# MicrocontrollerModule.net
KiCad netlist of a schematic drawn in EAGLE
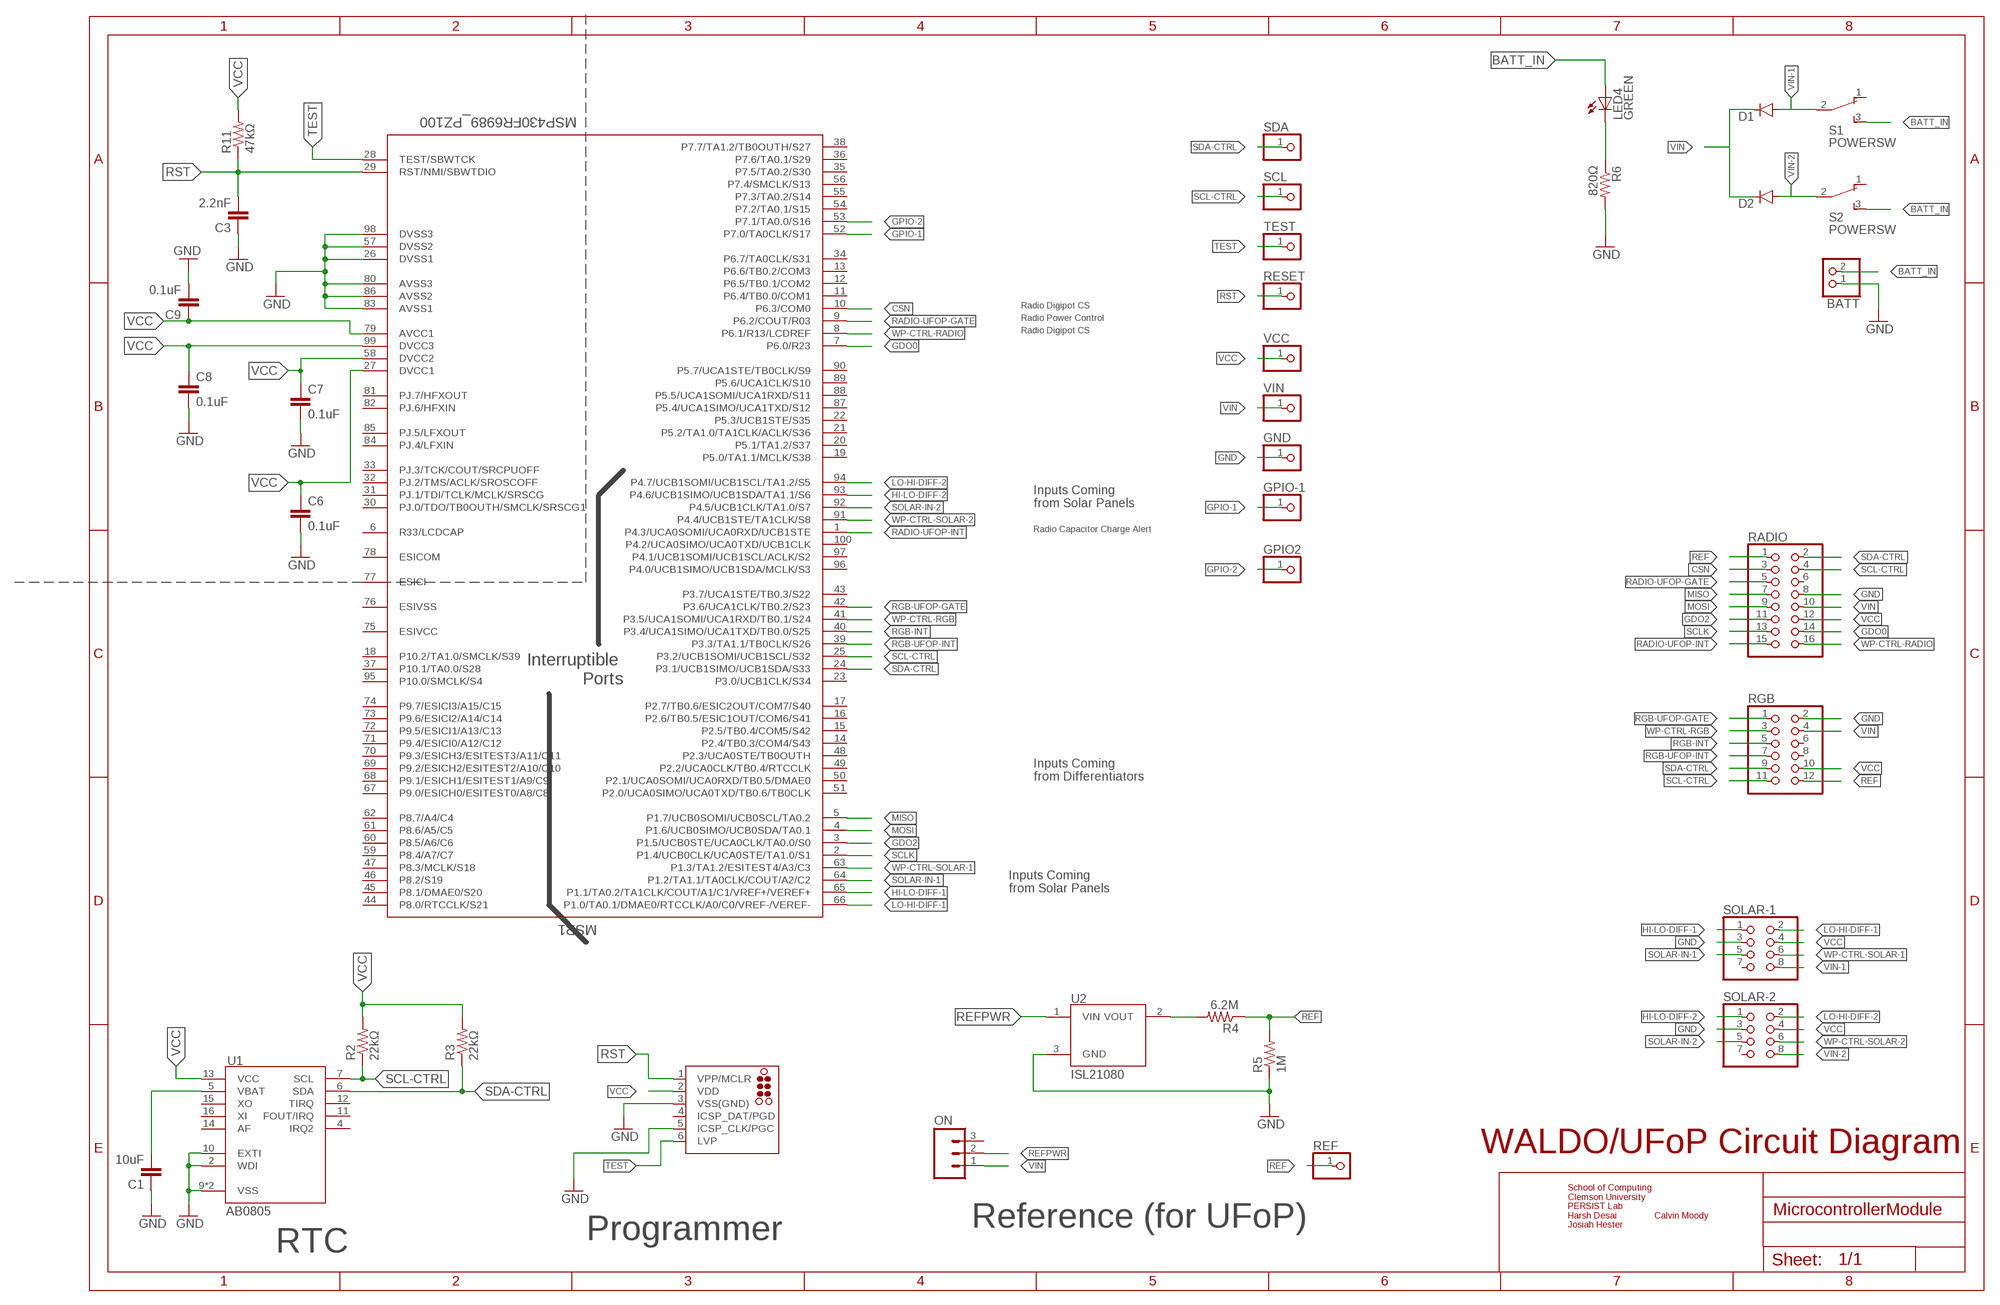
[diagram p0: schematic, sheet 1]

(export (version "E")
  (design (tool "Eeschema 10.0.6"))
  (components
    (comp (ref "BATT")
      (value "PINHD-1X2")
      (footprint "eagle-import:1X02")
      (libsource (lib "eagle-import") (part "PINHD-1X2"))
    )
    (comp (ref "C1")
      (value "10uF")
      (footprint "eagle-import:0805")
      (libsource (lib "eagle-import") (part "CAP0805"))
    )
    (comp (ref "C3")
      (value "2.2nF")
      (footprint "eagle-import:0805")
      (libsource (lib "eagle-import") (part "CAP0805"))
    )
    (comp (ref "C6")
      (value "0.1uF")
      (footprint "eagle-import:0805")
      (libsource (lib "eagle-import") (part "CAP0805"))
    )
    (comp (ref "C7")
      (value "0.1uF")
      (footprint "eagle-import:0805")
      (libsource (lib "eagle-import") (part "CAP0805"))
    )
    (comp (ref "C8")
      (value "0.1uF")
      (footprint "eagle-import:0805")
      (libsource (lib "eagle-import") (part "CAP0805"))
    )
    (comp (ref "C9")
      (value "0.1uF")
      (footprint "eagle-import:0805")
      (libsource (lib "eagle-import") (part "CAP0805"))
    )
    (comp (ref "D1")
      (value "DIODESOD523")
      (footprint "eagle-import:SOD523")
      (libsource (lib "eagle-import") (part "DIODESOD523"))
    )
    (comp (ref "D2")
      (value "DIODESOD523")
      (footprint "eagle-import:SOD523")
      (libsource (lib "eagle-import") (part "DIODESOD523"))
    )
    (comp (ref "GND")
      (value "PINHD-1X1")
      (footprint "eagle-import:1X01")
      (libsource (lib "eagle-import") (part "PINHD-1X1"))
    )
    (comp (ref "GPIO-1")
      (value "PINHD-1X1")
      (footprint "eagle-import:1X01")
      (libsource (lib "eagle-import") (part "PINHD-1X1"))
    )
    (comp (ref "GPIO2")
      (value "PINHD-1X1")
      (footprint "eagle-import:1X01")
      (libsource (lib "eagle-import") (part "PINHD-1X1"))
    )
    (comp (ref "J1")
      (value "TC2030-MCP-NL")
      (footprint "eagle-import:TC2030-MCP-NL")
      (libsource (lib "eagle-import") (part "TC2030-MCP-NL"))
    )
    (comp (ref "LED4")
      (value "GREEN")
      (footprint "eagle-import:CHIP-LED0805")
      (libsource (lib "eagle-import") (part "LEDCHIP-LED0805"))
    )
    (comp (ref "MSP1")
      (value "MSP430FR6989_PZ100")
      (footprint "eagle-import:PZ100")
      (libsource (lib "eagle-import") (part "MSP430FR6989_PZ100"))
    )
    (comp (ref "ON")
      (value "M03")
      (footprint "eagle-import:1X03-1.27MM")
      (libsource (lib "eagle-import") (part "M03"))
    )
    (comp (ref "R2")
      (value "22kΩ")
      (footprint "eagle-import:0805")
      (libsource (lib "eagle-import") (part "RESISTOR0805-RES"))
    )
    (comp (ref "R3")
      (value "22kΩ")
      (footprint "eagle-import:0805")
      (libsource (lib "eagle-import") (part "RESISTOR0805-RES"))
    )
    (comp (ref "R4")
      (value "6.2M")
      (footprint "eagle-import:0805")
      (libsource (lib "eagle-import") (part "RESISTOR0805-RES"))
    )
    (comp (ref "R5")
      (value "1M")
      (footprint "eagle-import:0805")
      (libsource (lib "eagle-import") (part "RESISTOR0805-RES"))
    )
    (comp (ref "R6")
      (value "820Ω")
      (footprint "eagle-import:0805")
      (libsource (lib "eagle-import") (part "RESISTOR0805-RES"))
    )
    (comp (ref "R11")
      (value "47kΩ")
      (footprint "eagle-import:0805")
      (libsource (lib "eagle-import") (part "RESISTOR0805-RES"))
    )
    (comp (ref "RADIO")
      (value "PINHD-2X8/90")
      (footprint "eagle-import:2X08_90")
      (libsource (lib "eagle-import") (part "PINHD-2X8/90"))
    )
    (comp (ref "REF")
      (value "PINHD-1X1")
      (footprint "eagle-import:1X01")
      (libsource (lib "eagle-import") (part "PINHD-1X1"))
    )
    (comp (ref "RESET")
      (value "PINHD-1X1")
      (footprint "eagle-import:1X01")
      (libsource (lib "eagle-import") (part "PINHD-1X1"))
    )
    (comp (ref "RGB")
      (value "PINHD-2X6/90")
      (footprint "eagle-import:2X06_90")
      (libsource (lib "eagle-import") (part "PINHD-2X6/90"))
    )
    (comp (ref "S1")
      (value "POWERSW")
      (footprint "eagle-import:TL3XYO")
      (libsource (lib "eagle-import") (part "POWERSW"))
    )
    (comp (ref "S2")
      (value "POWERSW")
      (footprint "eagle-import:TL3XYO")
      (libsource (lib "eagle-import") (part "POWERSW"))
    )
    (comp (ref "SCL")
      (value "PINHD-1X1")
      (footprint "eagle-import:1X01")
      (libsource (lib "eagle-import") (part "PINHD-1X1"))
    )
    (comp (ref "SDA")
      (value "PINHD-1X1")
      (footprint "eagle-import:1X01")
      (libsource (lib "eagle-import") (part "PINHD-1X1"))
    )
    (comp (ref "SOLAR-1")
      (value "PINHD-2X4/90")
      (footprint "eagle-import:2X04_90")
      (libsource (lib "eagle-import") (part "PINHD-2X4/90"))
    )
    (comp (ref "SOLAR-2")
      (value "PINHD-2X4/90")
      (footprint "eagle-import:2X04_90")
      (libsource (lib "eagle-import") (part "PINHD-2X4/90"))
    )
    (comp (ref "TEST")
      (value "PINHD-1X1")
      (footprint "eagle-import:1X01")
      (libsource (lib "eagle-import") (part "PINHD-1X1"))
    )
    (comp (ref "U1")
      (value "AB0805")
      (footprint "eagle-import:QFN16")
      (libsource (lib "eagle-import") (part "AB0805"))
    )
    (comp (ref "U2")
      (value "ISL21080")
      (footprint "eagle-import:SOT-23")
      (libsource (lib "eagle-import") (part "ISL21080"))
    )
    (comp (ref "VCC")
      (value "PINHD-1X1")
      (footprint "eagle-import:1X01")
      (libsource (lib "eagle-import") (part "PINHD-1X1"))
    )
    (comp (ref "VIN")
      (value "PINHD-1X1")
      (footprint "eagle-import:1X01")
      (libsource (lib "eagle-import") (part "PINHD-1X1"))
    )
  )
  (nets
    (net (code "1") (name "BATT_IN") (class "Default")
      (node (ref "BATT") (pin "2") (pinfunction "2_2") (pintype "passive"))
      (node (ref "LED4") (pin "A") (pinfunction "A_A") (pintype "passive"))
      (node (ref "S1") (pin "3") (pinfunction "S_3") (pintype "passive"))
      (node (ref "S2") (pin "3") (pinfunction "S_3") (pintype "passive"))
    )
    (net (code "2") (name "CSN") (class "Default")
      (node (ref "MSP1") (pin "10") (pinfunction "P6.3/COM0_10") (pintype "bidirectional"))
      (node (ref "RADIO") (pin "3") (pinfunction "3_3") (pintype "passive"))
    )
    (net (code "3") (name "GDO0") (class "Default")
      (node (ref "MSP1") (pin "7") (pinfunction "P6.0/R23_7") (pintype "bidirectional"))
      (node (ref "RADIO") (pin "14") (pinfunction "14_14") (pintype "passive"))
    )
    (net (code "4") (name "GDO2") (class "Default")
      (node (ref "MSP1") (pin "3") (pinfunction "P1.5/UCB0STE/UCA0CLK/TA0.0/S0_3") (pintype "bidirectional"))
      (node (ref "RADIO") (pin "11") (pinfunction "11_11") (pintype "passive"))
    )
    (net (code "5") (name "GND") (class "Default")
      (node (ref "BATT") (pin "1") (pinfunction "1_1") (pintype "passive"))
      (node (ref "C1") (pin "1") (pinfunction "1_1") (pintype "passive"))
      (node (ref "C3") (pin "1") (pinfunction "1_1") (pintype "passive"))
      (node (ref "C6") (pin "2") (pinfunction "2_2") (pintype "passive"))
      (node (ref "C7") (pin "2") (pinfunction "2_2") (pintype "passive"))
      (node (ref "C8") (pin "2") (pinfunction "2_2") (pintype "passive"))
      (node (ref "C9") (pin "2") (pinfunction "2_2") (pintype "passive"))
      (node (ref "GND") (pin "1") (pinfunction "1_1") (pintype "passive"))
      (node (ref "J1") (pin "3") (pinfunction "VSS(GND)_3") (pintype "power_in"))
      (node (ref "J1") (pin "5") (pinfunction "ICSP_CLK/PGC_5") (pintype "output"))
      (node (ref "MSP1") (pin "26") (pinfunction "DVSS1_26") (pintype "bidirectional"))
      (node (ref "MSP1") (pin "57") (pinfunction "DVSS2_57") (pintype "bidirectional"))
      (node (ref "MSP1") (pin "80") (pinfunction "AVSS3_80") (pintype "bidirectional"))
      (node (ref "MSP1") (pin "83") (pinfunction "AVSS1_83") (pintype "bidirectional"))
      (node (ref "MSP1") (pin "86") (pinfunction "AVSS2_86") (pintype "bidirectional"))
      (node (ref "MSP1") (pin "98") (pinfunction "DVSS3_98") (pintype "bidirectional"))
      (node (ref "R5") (pin "1") (pinfunction "1_1") (pintype "passive"))
      (node (ref "R6") (pin "2") (pinfunction "2_2") (pintype "passive"))
      (node (ref "RADIO") (pin "8") (pinfunction "8_8") (pintype "passive"))
      (node (ref "RGB") (pin "2") (pinfunction "2_2") (pintype "passive"))
      (node (ref "SOLAR-1") (pin "3") (pinfunction "3_3") (pintype "passive"))
      (node (ref "SOLAR-2") (pin "3") (pinfunction "3_3") (pintype "passive"))
      (node (ref "U1") (pin "10") (pinfunction "EXTI_10") (pintype "bidirectional"))
      (node (ref "U1") (pin "2") (pinfunction "WDI_2") (pintype "bidirectional"))
      (node (ref "U1") (pin "9") (pinfunction "VSS_9") (pintype "bidirectional"))
      (node (ref "U1") (pin "TH") (pinfunction "VSS_TH") (pintype "bidirectional"))
      (node (ref "U2") (pin "3") (pinfunction "GND_3") (pintype "bidirectional"))
    )
    (net (code "6") (name "GPIO-1") (class "Default")
      (node (ref "GPIO-1") (pin "1") (pinfunction "1_1") (pintype "passive"))
      (node (ref "MSP1") (pin "52") (pinfunction "P7.0/TA0CLK/S17_52") (pintype "bidirectional"))
    )
    (net (code "7") (name "GPIO-2") (class "Default")
      (node (ref "GPIO2") (pin "1") (pinfunction "1_1") (pintype "passive"))
      (node (ref "MSP1") (pin "53") (pinfunction "P7.1/TA0.0/S16_53") (pintype "bidirectional"))
    )
    (net (code "8") (name "HI-LO-DIFF-1") (class "Default")
      (node (ref "MSP1") (pin "65") (pinfunction "P1.1/TA0.2/TA1CLK/COUT/A1/C1/VREF+/VEREF+_65") (pintype "bidirectional"))
      (node (ref "SOLAR-1") (pin "1") (pinfunction "1_1") (pintype "passive"))
    )
    (net (code "9") (name "HI-LO-DIFF-2") (class "Default")
      (node (ref "MSP1") (pin "93") (pinfunction "P4.6/UCB1SIMO/UCB1SDA/TA1.1/S6_93") (pintype "bidirectional"))
      (node (ref "SOLAR-2") (pin "1") (pinfunction "1_1") (pintype "passive"))
    )
    (net (code "10") (name "LO-HI-DIFF-1") (class "Default")
      (node (ref "MSP1") (pin "66") (pinfunction "P1.0/TA0.1/DMAE0/RTCCLK/A0/C0/VREF-/VEREF-_66") (pintype "bidirectional"))
      (node (ref "SOLAR-1") (pin "2") (pinfunction "2_2") (pintype "passive"))
    )
    (net (code "11") (name "LO-HI-DIFF-2") (class "Default")
      (node (ref "MSP1") (pin "94") (pinfunction "P4.7/UCB1SOMI/UCB1SCL/TA1.2/S5_94") (pintype "bidirectional"))
      (node (ref "SOLAR-2") (pin "2") (pinfunction "2_2") (pintype "passive"))
    )
    (net (code "12") (name "MISO") (class "Default")
      (node (ref "MSP1") (pin "5") (pinfunction "P1.7/UCB0SOMI/UCB0SCL/TA0.2_5") (pintype "bidirectional"))
      (node (ref "RADIO") (pin "7") (pinfunction "7_7") (pintype "passive"))
    )
    (net (code "13") (name "MOSI") (class "Default")
      (node (ref "MSP1") (pin "4") (pinfunction "P1.6/UCB0SIMO/UCB0SDA/TA0.1_4") (pintype "bidirectional"))
      (node (ref "RADIO") (pin "9") (pinfunction "9_9") (pintype "passive"))
    )
    (net (code "14") (name "Net-(LED4-PadC)") (class "Default")
      (node (ref "LED4") (pin "C") (pinfunction "C_C") (pintype "passive"))
      (node (ref "R6") (pin "1") (pinfunction "1_1") (pintype "passive"))
    )
    (net (code "15") (name "Net-(U1-VBAT)") (class "Default")
      (node (ref "C1") (pin "2") (pinfunction "2_2") (pintype "passive"))
      (node (ref "U1") (pin "5") (pinfunction "VBAT_5") (pintype "bidirectional"))
    )
    (net (code "16") (name "Net-(U2-VOUT)") (class "Default")
      (node (ref "R4") (pin "2") (pinfunction "2_2") (pintype "passive"))
      (node (ref "U2") (pin "2") (pinfunction "VOUT_2") (pintype "bidirectional"))
    )
    (net (code "17") (name "RADIO-UFOP-GATE") (class "Default")
      (node (ref "MSP1") (pin "9") (pinfunction "P6.2/COUT/R03_9") (pintype "bidirectional"))
      (node (ref "RADIO") (pin "5") (pinfunction "5_5") (pintype "passive"))
    )
    (net (code "18") (name "RADIO-UFOP-INT") (class "Default")
      (node (ref "MSP1") (pin "1") (pinfunction "P4.3/UCA0SOMI/UCA0RXD/UCB1STE_1") (pintype "bidirectional"))
      (node (ref "RADIO") (pin "15") (pinfunction "15_15") (pintype "passive"))
    )
    (net (code "19") (name "REF") (class "Default")
      (node (ref "R4") (pin "1") (pinfunction "1_1") (pintype "passive"))
      (node (ref "R5") (pin "2") (pinfunction "2_2") (pintype "passive"))
      (node (ref "RADIO") (pin "1") (pinfunction "1_1") (pintype "passive"))
      (node (ref "REF") (pin "1") (pinfunction "1_1") (pintype "passive"))
      (node (ref "RGB") (pin "12") (pinfunction "12_12") (pintype "passive"))
    )
    (net (code "20") (name "REFPWR") (class "Default")
      (node (ref "ON") (pin "2") (pinfunction "2_2") (pintype "passive"))
      (node (ref "U2") (pin "1") (pinfunction "VIN_1") (pintype "bidirectional"))
    )
    (net (code "21") (name "RGB-INT") (class "Default")
      (node (ref "MSP1") (pin "40") (pinfunction "P3.4/UCA1SIMO/UCA1TXD/TB0.0/S25_40") (pintype "bidirectional"))
      (node (ref "RGB") (pin "5") (pinfunction "5_5") (pintype "passive"))
    )
    (net (code "22") (name "RGB-UFOP-GATE") (class "Default")
      (node (ref "MSP1") (pin "42") (pinfunction "P3.6/UCA1CLK/TB0.2/S23_42") (pintype "bidirectional"))
      (node (ref "RGB") (pin "1") (pinfunction "1_1") (pintype "passive"))
    )
    (net (code "23") (name "RGB-UFOP-INT") (class "Default")
      (node (ref "MSP1") (pin "39") (pinfunction "P3.3/TA1.1/TB0CLK/S26_39") (pintype "bidirectional"))
      (node (ref "RGB") (pin "7") (pinfunction "7_7") (pintype "passive"))
    )
    (net (code "24") (name "RST") (class "Default")
      (node (ref "C3") (pin "2") (pinfunction "2_2") (pintype "passive"))
      (node (ref "J1") (pin "1") (pinfunction "VPP/MCLR_1") (pintype "passive"))
      (node (ref "MSP1") (pin "29") (pinfunction "RST/NMI/SBWTDIO_29") (pintype "bidirectional"))
      (node (ref "R11") (pin "1") (pinfunction "1_1") (pintype "passive"))
      (node (ref "RESET") (pin "1") (pinfunction "1_1") (pintype "passive"))
    )
    (net (code "25") (name "SCL-CTRL") (class "Default")
      (node (ref "MSP1") (pin "25") (pinfunction "P3.2/UCB1SOMI/UCB1SCL/S32_25") (pintype "bidirectional"))
      (node (ref "R2") (pin "1") (pinfunction "1_1") (pintype "passive"))
      (node (ref "RADIO") (pin "4") (pinfunction "4_4") (pintype "passive"))
      (node (ref "RGB") (pin "11") (pinfunction "11_11") (pintype "passive"))
      (node (ref "SCL") (pin "1") (pinfunction "1_1") (pintype "passive"))
      (node (ref "U1") (pin "7") (pinfunction "SCL_7") (pintype "bidirectional"))
    )
    (net (code "26") (name "SCLK") (class "Default")
      (node (ref "MSP1") (pin "2") (pinfunction "P1.4/UCB0CLK/UCA0STE/TA1.0/S1_2") (pintype "bidirectional"))
      (node (ref "RADIO") (pin "13") (pinfunction "13_13") (pintype "passive"))
    )
    (net (code "27") (name "SDA-CTRL") (class "Default")
      (node (ref "MSP1") (pin "24") (pinfunction "P3.1/UCB1SIMO/UCB1SDA/S33_24") (pintype "bidirectional"))
      (node (ref "R3") (pin "1") (pinfunction "1_1") (pintype "passive"))
      (node (ref "RADIO") (pin "2") (pinfunction "2_2") (pintype "passive"))
      (node (ref "RGB") (pin "9") (pinfunction "9_9") (pintype "passive"))
      (node (ref "SDA") (pin "1") (pinfunction "1_1") (pintype "passive"))
      (node (ref "U1") (pin "6") (pinfunction "SDA_6") (pintype "bidirectional"))
    )
    (net (code "28") (name "SOLAR-IN-1") (class "Default")
      (node (ref "MSP1") (pin "64") (pinfunction "P1.2/TA1.1/TA0CLK/COUT/A2/C2_64") (pintype "bidirectional"))
      (node (ref "SOLAR-1") (pin "5") (pinfunction "5_5") (pintype "passive"))
    )
    (net (code "29") (name "SOLAR-IN-2") (class "Default")
      (node (ref "MSP1") (pin "92") (pinfunction "P4.5/UCB1CLK/TA1.0/S7_92") (pintype "bidirectional"))
      (node (ref "SOLAR-2") (pin "5") (pinfunction "5_5") (pintype "passive"))
    )
    (net (code "30") (name "TEST") (class "Default")
      (node (ref "J1") (pin "6") (pinfunction "LVP_6") (pintype "bidirectional"))
      (node (ref "MSP1") (pin "28") (pinfunction "TEST/SBWTCK_28") (pintype "bidirectional"))
      (node (ref "TEST") (pin "1") (pinfunction "1_1") (pintype "passive"))
    )
    (net (code "31") (name "VCC") (class "Default")
      (node (ref "C6") (pin "1") (pinfunction "1_1") (pintype "passive"))
      (node (ref "C7") (pin "1") (pinfunction "1_1") (pintype "passive"))
      (node (ref "C8") (pin "1") (pinfunction "1_1") (pintype "passive"))
      (node (ref "C9") (pin "1") (pinfunction "1_1") (pintype "passive"))
      (node (ref "J1") (pin "2") (pinfunction "VDD_2") (pintype "power_in"))
      (node (ref "MSP1") (pin "27") (pinfunction "DVCC1_27") (pintype "bidirectional"))
      (node (ref "MSP1") (pin "58") (pinfunction "DVCC2_58") (pintype "bidirectional"))
      (node (ref "MSP1") (pin "79") (pinfunction "AVCC1_79") (pintype "bidirectional"))
      (node (ref "MSP1") (pin "99") (pinfunction "DVCC3_99") (pintype "bidirectional"))
      (node (ref "R11") (pin "2") (pinfunction "2_2") (pintype "passive"))
      (node (ref "R2") (pin "2") (pinfunction "2_2") (pintype "passive"))
      (node (ref "R3") (pin "2") (pinfunction "2_2") (pintype "passive"))
      (node (ref "RADIO") (pin "12") (pinfunction "12_12") (pintype "passive"))
      (node (ref "RGB") (pin "10") (pinfunction "10_10") (pintype "passive"))
      (node (ref "SOLAR-1") (pin "4") (pinfunction "4_4") (pintype "passive"))
      (node (ref "SOLAR-2") (pin "4") (pinfunction "4_4") (pintype "passive"))
      (node (ref "U1") (pin "13") (pinfunction "VCC_13") (pintype "bidirectional"))
      (node (ref "VCC") (pin "1") (pinfunction "1_1") (pintype "passive"))
    )
    (net (code "32") (name "VIN") (class "Default")
      (node (ref "D1") (pin "C") (pinfunction "C_C") (pintype "passive"))
      (node (ref "D2") (pin "C") (pinfunction "C_C") (pintype "passive"))
      (node (ref "ON") (pin "1") (pinfunction "1_1") (pintype "passive"))
      (node (ref "RADIO") (pin "10") (pinfunction "10_10") (pintype "passive"))
      (node (ref "RGB") (pin "4") (pinfunction "4_4") (pintype "passive"))
      (node (ref "VIN") (pin "1") (pinfunction "1_1") (pintype "passive"))
    )
    (net (code "33") (name "VIN-1") (class "Default")
      (node (ref "D1") (pin "A") (pinfunction "A_A") (pintype "passive"))
      (node (ref "S1") (pin "2") (pinfunction "P_2") (pintype "passive"))
      (node (ref "SOLAR-1") (pin "8") (pinfunction "8_8") (pintype "passive"))
    )
    (net (code "34") (name "VIN-2") (class "Default")
      (node (ref "D2") (pin "A") (pinfunction "A_A") (pintype "passive"))
      (node (ref "S2") (pin "2") (pinfunction "P_2") (pintype "passive"))
      (node (ref "SOLAR-2") (pin "8") (pinfunction "8_8") (pintype "passive"))
    )
    (net (code "35") (name "WP-CTRL-RADIO") (class "Default")
      (node (ref "MSP1") (pin "8") (pinfunction "P6.1/R13/LCDREF_8") (pintype "bidirectional"))
      (node (ref "RADIO") (pin "16") (pinfunction "16_16") (pintype "passive"))
    )
    (net (code "36") (name "WP-CTRL-RGB") (class "Default")
      (node (ref "MSP1") (pin "41") (pinfunction "P3.5/UCA1SOMI/UCA1RXD/TB0.1/S24_41") (pintype "bidirectional"))
      (node (ref "RGB") (pin "3") (pinfunction "3_3") (pintype "passive"))
    )
    (net (code "37") (name "WP-CTRL-SOLAR-1") (class "Default")
      (node (ref "MSP1") (pin "63") (pinfunction "P1.3/TA1.2/ESITEST4/A3/C3_63") (pintype "bidirectional"))
      (node (ref "SOLAR-1") (pin "6") (pinfunction "6_6") (pintype "passive"))
    )
    (net (code "38") (name "WP-CTRL-SOLAR-2") (class "Default")
      (node (ref "MSP1") (pin "91") (pinfunction "P4.4/UCB1STE/TA1CLK/S8_91") (pintype "bidirectional"))
      (node (ref "SOLAR-2") (pin "6") (pinfunction "6_6") (pintype "passive"))
    )
    (net (code "39") (name "unconnected-(J1-ICSP_DAT{slash}PGD-Pad4)") (class "Default")
      (node (ref "J1") (pin "4") (pinfunction "ICSP_DAT/PGD_4") (pintype "bidirectional"))
    )
    (net (code "40") (name "unconnected-(MSP1-ESICI-Pad77)") (class "Default")
      (node (ref "MSP1") (pin "77") (pinfunction "ESICI_77") (pintype "bidirectional"))
    )
    (net (code "41") (name "unconnected-(MSP1-ESICOM-Pad78)") (class "Default")
      (node (ref "MSP1") (pin "78") (pinfunction "ESICOM_78") (pintype "bidirectional"))
    )
    (net (code "42") (name "unconnected-(MSP1-ESIVCC-Pad75)") (class "Default")
      (node (ref "MSP1") (pin "75") (pinfunction "ESIVCC_75") (pintype "bidirectional"))
    )
    (net (code "43") (name "unconnected-(MSP1-ESIVSS-Pad76)") (class "Default")
      (node (ref "MSP1") (pin "76") (pinfunction "ESIVSS_76") (pintype "bidirectional"))
    )
    (net (code "44") (name "unconnected-(MSP1-P2.0{slash}UCA0SIMO{slash}UCA0TXD{slash}TB0.6{slash}TB0CLK-Pad51)") (class "Default")
      (node (ref "MSP1") (pin "51") (pinfunction "P2.0/UCA0SIMO/UCA0TXD/TB0.6/TB0CLK_51") (pintype "bidirectional"))
    )
    (net (code "45") (name "unconnected-(MSP1-P2.1{slash}UCA0SOMI{slash}UCA0RXD{slash}TB0.5{slash}DMAE0-Pad50)") (class "Default")
      (node (ref "MSP1") (pin "50") (pinfunction "P2.1/UCA0SOMI/UCA0RXD/TB0.5/DMAE0_50") (pintype "bidirectional"))
    )
    (net (code "46") (name "unconnected-(MSP1-P2.2{slash}UCA0CLK{slash}TB0.4{slash}RTCCLK-Pad49)") (class "Default")
      (node (ref "MSP1") (pin "49") (pinfunction "P2.2/UCA0CLK/TB0.4/RTCCLK_49") (pintype "bidirectional"))
    )
    (net (code "47") (name "unconnected-(MSP1-P2.3{slash}UCA0STE{slash}TB0OUTH-Pad48)") (class "Default")
      (node (ref "MSP1") (pin "48") (pinfunction "P2.3/UCA0STE/TB0OUTH_48") (pintype "bidirectional"))
    )
    (net (code "48") (name "unconnected-(MSP1-P2.4{slash}TB0.3{slash}COM4{slash}S43-Pad14)") (class "Default")
      (node (ref "MSP1") (pin "14") (pinfunction "P2.4/TB0.3/COM4/S43_14") (pintype "bidirectional"))
    )
    (net (code "49") (name "unconnected-(MSP1-P2.5{slash}TB0.4{slash}COM5{slash}S42-Pad15)") (class "Default")
      (node (ref "MSP1") (pin "15") (pinfunction "P2.5/TB0.4/COM5/S42_15") (pintype "bidirectional"))
    )
    (net (code "50") (name "unconnected-(MSP1-P2.6{slash}TB0.5{slash}ESIC1OUT{slash}COM6{slash}S41-Pad16)") (class "Default")
      (node (ref "MSP1") (pin "16") (pinfunction "P2.6/TB0.5/ESIC1OUT/COM6/S41_16") (pintype "bidirectional"))
    )
    (net (code "51") (name "unconnected-(MSP1-P2.7{slash}TB0.6{slash}ESIC2OUT{slash}COM7{slash}S40-Pad17)") (class "Default")
      (node (ref "MSP1") (pin "17") (pinfunction "P2.7/TB0.6/ESIC2OUT/COM7/S40_17") (pintype "bidirectional"))
    )
    (net (code "52") (name "unconnected-(MSP1-P3.0{slash}UCB1CLK{slash}S34-Pad23)") (class "Default")
      (node (ref "MSP1") (pin "23") (pinfunction "P3.0/UCB1CLK/S34_23") (pintype "bidirectional"))
    )
    (net (code "53") (name "unconnected-(MSP1-P3.7{slash}UCA1STE{slash}TB0.3{slash}S22-Pad43)") (class "Default")
      (node (ref "MSP1") (pin "43") (pinfunction "P3.7/UCA1STE/TB0.3/S22_43") (pintype "bidirectional"))
    )
    (net (code "54") (name "unconnected-(MSP1-P4.0{slash}UCB1SIMO{slash}UCB1SDA{slash}MCLK{slash}S3-Pad96)") (class "Default")
      (node (ref "MSP1") (pin "96") (pinfunction "P4.0/UCB1SIMO/UCB1SDA/MCLK/S3_96") (pintype "bidirectional"))
    )
    (net (code "55") (name "unconnected-(MSP1-P4.1{slash}UCB1SOMI{slash}UCB1SCL{slash}ACLK{slash}S2-Pad97)") (class "Default")
      (node (ref "MSP1") (pin "97") (pinfunction "P4.1/UCB1SOMI/UCB1SCL/ACLK/S2_97") (pintype "bidirectional"))
    )
    (net (code "56") (name "unconnected-(MSP1-P4.2{slash}UCA0SIMO{slash}UCA0TXD{slash}UCB1CLK-Pad100)") (class "Default")
      (node (ref "MSP1") (pin "100") (pinfunction "P4.2/UCA0SIMO/UCA0TXD/UCB1CLK_100") (pintype "bidirectional"))
    )
    (net (code "57") (name "unconnected-(MSP1-P5.0{slash}TA1.1{slash}MCLK{slash}S38-Pad19)") (class "Default")
      (node (ref "MSP1") (pin "19") (pinfunction "P5.0/TA1.1/MCLK/S38_19") (pintype "bidirectional"))
    )
    (net (code "58") (name "unconnected-(MSP1-P5.1{slash}TA1.2{slash}S37-Pad20)") (class "Default")
      (node (ref "MSP1") (pin "20") (pinfunction "P5.1/TA1.2/S37_20") (pintype "bidirectional"))
    )
    (net (code "59") (name "unconnected-(MSP1-P5.2{slash}TA1.0{slash}TA1CLK{slash}ACLK{slash}S36-Pad21)") (class "Default")
      (node (ref "MSP1") (pin "21") (pinfunction "P5.2/TA1.0/TA1CLK/ACLK/S36_21") (pintype "bidirectional"))
    )
    (net (code "60") (name "unconnected-(MSP1-P5.3{slash}UCB1STE{slash}S35-Pad22)") (class "Default")
      (node (ref "MSP1") (pin "22") (pinfunction "P5.3/UCB1STE/S35_22") (pintype "bidirectional"))
    )
    (net (code "61") (name "unconnected-(MSP1-P5.4{slash}UCA1SIMO{slash}UCA1TXD{slash}S12-Pad87)") (class "Default")
      (node (ref "MSP1") (pin "87") (pinfunction "P5.4/UCA1SIMO/UCA1TXD/S12_87") (pintype "bidirectional"))
    )
    (net (code "62") (name "unconnected-(MSP1-P5.5{slash}UCA1SOMI{slash}UCA1RXD{slash}S11-Pad88)") (class "Default")
      (node (ref "MSP1") (pin "88") (pinfunction "P5.5/UCA1SOMI/UCA1RXD/S11_88") (pintype "bidirectional"))
    )
    (net (code "63") (name "unconnected-(MSP1-P5.6{slash}UCA1CLK{slash}S10-Pad89)") (class "Default")
      (node (ref "MSP1") (pin "89") (pinfunction "P5.6/UCA1CLK/S10_89") (pintype "bidirectional"))
    )
    (net (code "64") (name "unconnected-(MSP1-P5.7{slash}UCA1STE{slash}TB0CLK{slash}S9-Pad90)") (class "Default")
      (node (ref "MSP1") (pin "90") (pinfunction "P5.7/UCA1STE/TB0CLK/S9_90") (pintype "bidirectional"))
    )
    (net (code "65") (name "unconnected-(MSP1-P6.4{slash}TB0.0{slash}COM1-Pad11)") (class "Default")
      (node (ref "MSP1") (pin "11") (pinfunction "P6.4/TB0.0/COM1_11") (pintype "bidirectional"))
    )
    (net (code "66") (name "unconnected-(MSP1-P6.5{slash}TB0.1{slash}COM2-Pad12)") (class "Default")
      (node (ref "MSP1") (pin "12") (pinfunction "P6.5/TB0.1/COM2_12") (pintype "bidirectional"))
    )
    (net (code "67") (name "unconnected-(MSP1-P6.6{slash}TB0.2{slash}COM3-Pad13)") (class "Default")
      (node (ref "MSP1") (pin "13") (pinfunction "P6.6/TB0.2/COM3_13") (pintype "bidirectional"))
    )
    (net (code "68") (name "unconnected-(MSP1-P6.7{slash}TA0CLK{slash}S31-Pad34)") (class "Default")
      (node (ref "MSP1") (pin "34") (pinfunction "P6.7/TA0CLK/S31_34") (pintype "bidirectional"))
    )
    (net (code "69") (name "unconnected-(MSP1-P7.2{slash}TA0.1{slash}S15-Pad54)") (class "Default")
      (node (ref "MSP1") (pin "54") (pinfunction "P7.2/TA0.1/S15_54") (pintype "bidirectional"))
    )
    (net (code "70") (name "unconnected-(MSP1-P7.3{slash}TA0.2{slash}S14-Pad55)") (class "Default")
      (node (ref "MSP1") (pin "55") (pinfunction "P7.3/TA0.2/S14_55") (pintype "bidirectional"))
    )
    (net (code "71") (name "unconnected-(MSP1-P7.4{slash}SMCLK{slash}S13-Pad56)") (class "Default")
      (node (ref "MSP1") (pin "56") (pinfunction "P7.4/SMCLK/S13_56") (pintype "bidirectional"))
    )
    (net (code "72") (name "unconnected-(MSP1-P7.5{slash}TA0.2{slash}S30-Pad35)") (class "Default")
      (node (ref "MSP1") (pin "35") (pinfunction "P7.5/TA0.2/S30_35") (pintype "bidirectional"))
    )
    (net (code "73") (name "unconnected-(MSP1-P7.6{slash}TA0.1{slash}S29-Pad36)") (class "Default")
      (node (ref "MSP1") (pin "36") (pinfunction "P7.6/TA0.1/S29_36") (pintype "bidirectional"))
    )
    (net (code "74") (name "unconnected-(MSP1-P7.7{slash}TA1.2{slash}TB0OUTH{slash}S27-Pad38)") (class "Default")
      (node (ref "MSP1") (pin "38") (pinfunction "P7.7/TA1.2/TB0OUTH/S27_38") (pintype "bidirectional"))
    )
    (net (code "75") (name "unconnected-(MSP1-P8.0{slash}RTCCLK{slash}S21-Pad44)") (class "Default")
      (node (ref "MSP1") (pin "44") (pinfunction "P8.0/RTCCLK/S21_44") (pintype "bidirectional"))
    )
    (net (code "76") (name "unconnected-(MSP1-P8.1{slash}DMAE0{slash}S20-Pad45)") (class "Default")
      (node (ref "MSP1") (pin "45") (pinfunction "P8.1/DMAE0/S20_45") (pintype "bidirectional"))
    )
    (net (code "77") (name "unconnected-(MSP1-P8.2{slash}S19-Pad46)") (class "Default")
      (node (ref "MSP1") (pin "46") (pinfunction "P8.2/S19_46") (pintype "bidirectional"))
    )
    (net (code "78") (name "unconnected-(MSP1-P8.3{slash}MCLK{slash}S18-Pad47)") (class "Default")
      (node (ref "MSP1") (pin "47") (pinfunction "P8.3/MCLK/S18_47") (pintype "bidirectional"))
    )
    (net (code "79") (name "unconnected-(MSP1-P8.4{slash}A7{slash}C7-Pad59)") (class "Default")
      (node (ref "MSP1") (pin "59") (pinfunction "P8.4/A7/C7_59") (pintype "bidirectional"))
    )
    (net (code "80") (name "unconnected-(MSP1-P8.5{slash}A6{slash}C6-Pad60)") (class "Default")
      (node (ref "MSP1") (pin "60") (pinfunction "P8.5/A6/C6_60") (pintype "bidirectional"))
    )
    (net (code "81") (name "unconnected-(MSP1-P8.6{slash}A5{slash}C5-Pad61)") (class "Default")
      (node (ref "MSP1") (pin "61") (pinfunction "P8.6/A5/C5_61") (pintype "bidirectional"))
    )
    (net (code "82") (name "unconnected-(MSP1-P8.7{slash}A4{slash}C4-Pad62)") (class "Default")
      (node (ref "MSP1") (pin "62") (pinfunction "P8.7/A4/C4_62") (pintype "bidirectional"))
    )
    (net (code "83") (name "unconnected-(MSP1-P9.0{slash}ESICH0{slash}ESITEST0{slash}A8{slash}C8-Pad67)") (class "Default")
      (node (ref "MSP1") (pin "67") (pinfunction "P9.0/ESICH0/ESITEST0/A8/C8_67") (pintype "bidirectional"))
    )
    (net (code "84") (name "unconnected-(MSP1-P9.1{slash}ESICH1{slash}ESITEST1{slash}A9{slash}C9-Pad68)") (class "Default")
      (node (ref "MSP1") (pin "68") (pinfunction "P9.1/ESICH1/ESITEST1/A9/C9_68") (pintype "bidirectional"))
    )
    (net (code "85") (name "unconnected-(MSP1-P9.2{slash}ESICH2{slash}ESITEST2{slash}A10{slash}C10-Pad69)") (class "Default")
      (node (ref "MSP1") (pin "69") (pinfunction "P9.2/ESICH2/ESITEST2/A10/C10_69") (pintype "bidirectional"))
    )
    (net (code "86") (name "unconnected-(MSP1-P9.3{slash}ESICH3{slash}ESITEST3{slash}A11{slash}C11-Pad70)") (class "Default")
      (node (ref "MSP1") (pin "70") (pinfunction "P9.3/ESICH3/ESITEST3/A11/C11_70") (pintype "bidirectional"))
    )
    (net (code "87") (name "unconnected-(MSP1-P9.4{slash}ESICI0{slash}A12{slash}C12-Pad71)") (class "Default")
      (node (ref "MSP1") (pin "71") (pinfunction "P9.4/ESICI0/A12/C12_71") (pintype "bidirectional"))
    )
    (net (code "88") (name "unconnected-(MSP1-P9.5{slash}ESICI1{slash}A13{slash}C13-Pad72)") (class "Default")
      (node (ref "MSP1") (pin "72") (pinfunction "P9.5/ESICI1/A13/C13_72") (pintype "bidirectional"))
    )
    (net (code "89") (name "unconnected-(MSP1-P9.6{slash}ESICI2{slash}A14{slash}C14-Pad73)") (class "Default")
      (node (ref "MSP1") (pin "73") (pinfunction "P9.6/ESICI2/A14/C14_73") (pintype "bidirectional"))
    )
    (net (code "90") (name "unconnected-(MSP1-P9.7{slash}ESICI3{slash}A15{slash}C15-Pad74)") (class "Default")
      (node (ref "MSP1") (pin "74") (pinfunction "P9.7/ESICI3/A15/C15_74") (pintype "bidirectional"))
    )
    (net (code "91") (name "unconnected-(MSP1-P10.0{slash}SMCLK{slash}S4-Pad95)") (class "Default")
      (node (ref "MSP1") (pin "95") (pinfunction "P10.0/SMCLK/S4_95") (pintype "bidirectional"))
    )
    (net (code "92") (name "unconnected-(MSP1-P10.1{slash}TA0.0{slash}S28-Pad37)") (class "Default")
      (node (ref "MSP1") (pin "37") (pinfunction "P10.1/TA0.0/S28_37") (pintype "bidirectional"))
    )
    (net (code "93") (name "unconnected-(MSP1-P10.2{slash}TA1.0{slash}SMCLK{slash}S39-Pad18)") (class "Default")
      (node (ref "MSP1") (pin "18") (pinfunction "P10.2/TA1.0/SMCLK/S39_18") (pintype "bidirectional"))
    )
    (net (code "94") (name "unconnected-(MSP1-PJ.0{slash}TDO{slash}TB0OUTH{slash}SMCLK{slash}SRSCG1-Pad30)") (class "Default")
      (node (ref "MSP1") (pin "30") (pinfunction "PJ.0/TDO/TB0OUTH/SMCLK/SRSCG1_30") (pintype "bidirectional"))
    )
    (net (code "95") (name "unconnected-(MSP1-PJ.1{slash}TDI{slash}TCLK{slash}MCLK{slash}SRSCG-Pad31)") (class "Default")
      (node (ref "MSP1") (pin "31") (pinfunction "PJ.1/TDI/TCLK/MCLK/SRSCG_31") (pintype "bidirectional"))
    )
    (net (code "96") (name "unconnected-(MSP1-PJ.2{slash}TMS{slash}ACLK{slash}SROSCOFF-Pad32)") (class "Default")
      (node (ref "MSP1") (pin "32") (pinfunction "PJ.2/TMS/ACLK/SROSCOFF_32") (pintype "bidirectional"))
    )
    (net (code "97") (name "unconnected-(MSP1-PJ.3{slash}TCK{slash}COUT{slash}SRCPUOFF-Pad33)") (class "Default")
      (node (ref "MSP1") (pin "33") (pinfunction "PJ.3/TCK/COUT/SRCPUOFF_33") (pintype "bidirectional"))
    )
    (net (code "98") (name "unconnected-(MSP1-PJ.4{slash}LFXIN-Pad84)") (class "Default")
      (node (ref "MSP1") (pin "84") (pinfunction "PJ.4/LFXIN_84") (pintype "bidirectional"))
    )
    (net (code "99") (name "unconnected-(MSP1-PJ.5{slash}LFXOUT-Pad85)") (class "Default")
      (node (ref "MSP1") (pin "85") (pinfunction "PJ.5/LFXOUT_85") (pintype "bidirectional"))
    )
    (net (code "100") (name "unconnected-(MSP1-PJ.6{slash}HFXIN-Pad82)") (class "Default")
      (node (ref "MSP1") (pin "82") (pinfunction "PJ.6/HFXIN_82") (pintype "bidirectional"))
    )
    (net (code "101") (name "unconnected-(MSP1-PJ.7{slash}HFXOUT-Pad81)") (class "Default")
      (node (ref "MSP1") (pin "81") (pinfunction "PJ.7/HFXOUT_81") (pintype "bidirectional"))
    )
    (net (code "102") (name "unconnected-(MSP1-R33{slash}LCDCAP-Pad6)") (class "Default")
      (node (ref "MSP1") (pin "6") (pinfunction "R33/LCDCAP_6") (pintype "bidirectional"))
    )
    (net (code "103") (name "unconnected-(ON-Pad3)") (class "Default")
      (node (ref "ON") (pin "3") (pinfunction "3_3") (pintype "passive"))
    )
    (net (code "104") (name "unconnected-(RADIO-Pad6)") (class "Default")
      (node (ref "RADIO") (pin "6") (pinfunction "6_6") (pintype "passive"))
    )
    (net (code "105") (name "unconnected-(RGB-Pad6)") (class "Default")
      (node (ref "RGB") (pin "6") (pinfunction "6_6") (pintype "passive"))
    )
    (net (code "106") (name "unconnected-(RGB-Pad8)") (class "Default")
      (node (ref "RGB") (pin "8") (pinfunction "8_8") (pintype "passive"))
    )
    (net (code "107") (name "unconnected-(S1-O-Pad1)") (class "Default")
      (node (ref "S1") (pin "1") (pinfunction "O_1") (pintype "passive"))
    )
    (net (code "108") (name "unconnected-(S2-O-Pad1)") (class "Default")
      (node (ref "S2") (pin "1") (pinfunction "O_1") (pintype "passive"))
    )
    (net (code "109") (name "unconnected-(SOLAR-1-Pad7)") (class "Default")
      (node (ref "SOLAR-1") (pin "7") (pinfunction "7_7") (pintype "passive"))
    )
    (net (code "110") (name "unconnected-(SOLAR-2-Pad7)") (class "Default")
      (node (ref "SOLAR-2") (pin "7") (pinfunction "7_7") (pintype "passive"))
    )
    (net (code "111") (name "unconnected-(U1-AF-Pad14)") (class "Default")
      (node (ref "U1") (pin "14") (pinfunction "AF_14") (pintype "bidirectional"))
    )
    (net (code "112") (name "unconnected-(U1-FOUT{slash}IRQ-Pad11)") (class "Default")
      (node (ref "U1") (pin "11") (pinfunction "FOUT/IRQ_11") (pintype "bidirectional"))
    )
    (net (code "113") (name "unconnected-(U1-IRQ2-Pad4)") (class "Default")
      (node (ref "U1") (pin "4") (pinfunction "IRQ2_4") (pintype "bidirectional"))
    )
    (net (code "114") (name "unconnected-(U1-TIRQ-Pad12)") (class "Default")
      (node (ref "U1") (pin "12") (pinfunction "TIRQ_12") (pintype "bidirectional"))
    )
    (net (code "115") (name "unconnected-(U1-XI-Pad16)") (class "Default")
      (node (ref "U1") (pin "16") (pinfunction "XI_16") (pintype "bidirectional"))
    )
    (net (code "116") (name "unconnected-(U1-XO-Pad15)") (class "Default")
      (node (ref "U1") (pin "15") (pinfunction "XO_15") (pintype "bidirectional"))
    )
  )
)
